# Tead_Aliens_64A_Audio.net
KiCad netlist of a schematic drawn in Altium Designer
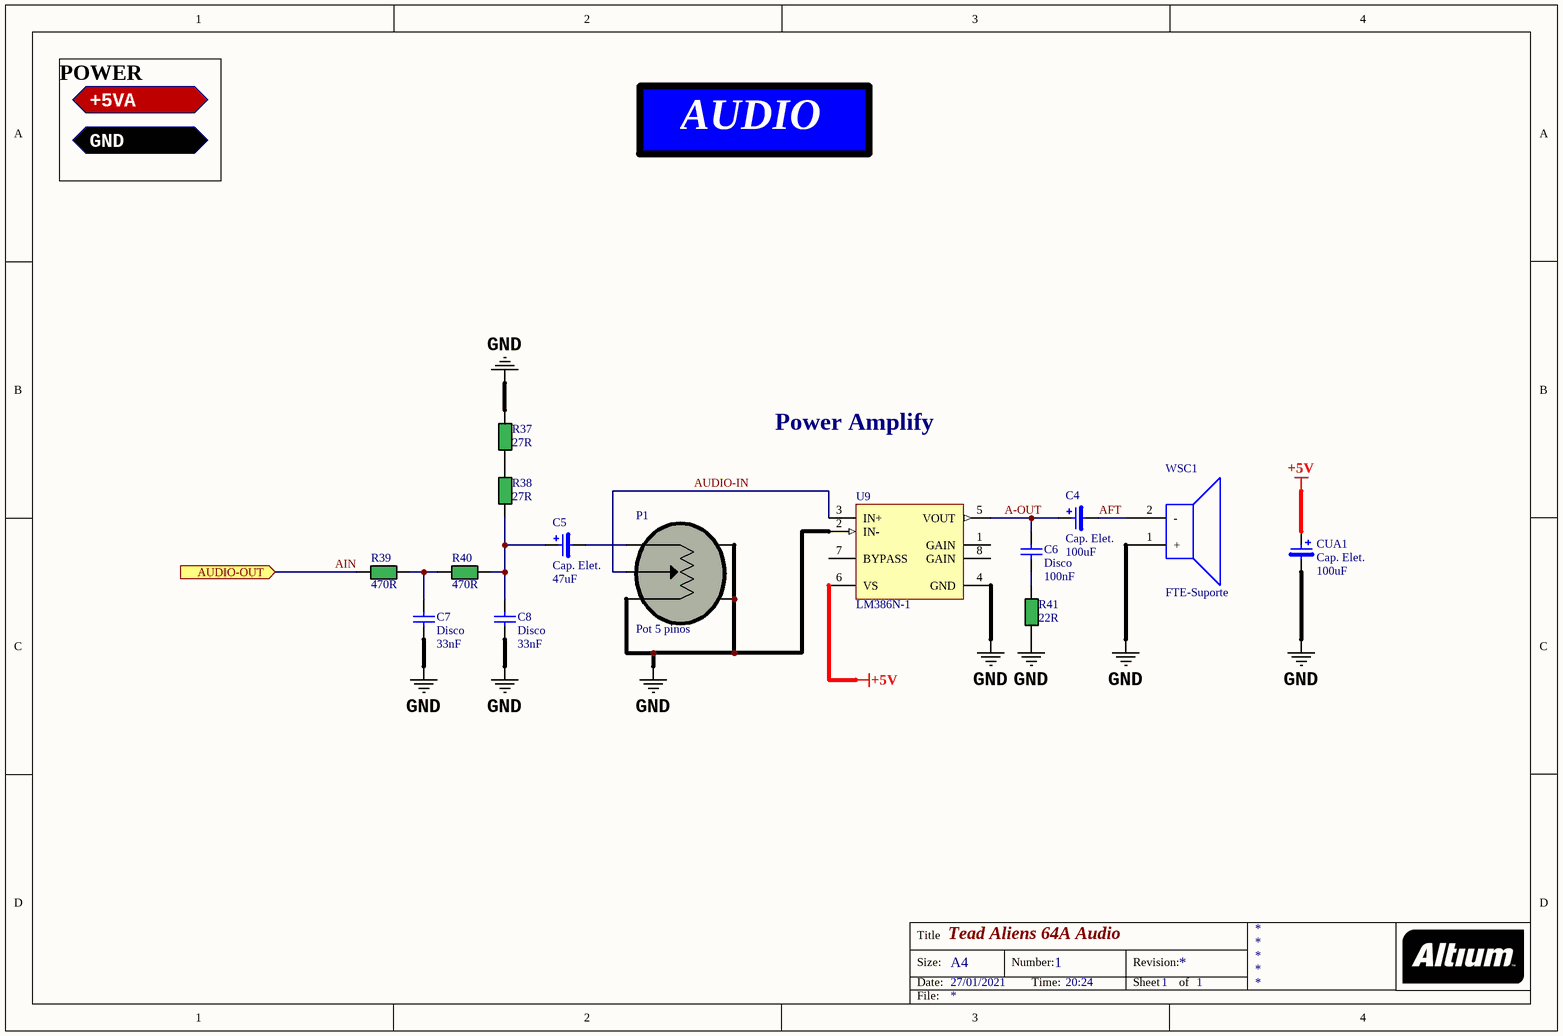
[diagram p0: Tead_Aliens_64A_Audio.SchDoc]

(export (version "E")
  (design (tool "Eeschema 10.0.6"))
  (components
    (comp (ref "C4")
      (value "Cap. Elet.")
      (footprint "CAP_RADIAL_2_10_16")
      (description "Capacitor Radial Eletrolitico")
      (fields (field (name "ALTIUM_VALUE") "100uF"))
      (libsource (lib "NEPERMATH") (part "CAP_RADIAL_ELETROLITICO"))
    )
    (comp (ref "C5")
      (value "Cap. Elet.")
      (footprint "CAP ELE RAD 11mm H")
      (description "Capacitor Radial Eletrolitico")
      (fields (field (name "ALTIUM_VALUE") "47uF"))
      (libsource (lib "NEPERMATH") (part "CAP_RADIAL_ELETROLITICO"))
    )
    (comp (ref "C6")
      (value "Disco")
      (footprint "CAP CER DISK 3MM")
      (description "SMD Capacitor 1210 size")
      (fields (field (name "ALTIUM_VALUE") "100nF"))
      (libsource (lib "NEPERMATH") (part "CAP_DISCO"))
    )
    (comp (ref "C7")
      (value "Disco")
      (footprint "CAP CER DISK 3MM")
      (description "SMD Capacitor 1210 size")
      (fields (field (name "ALTIUM_VALUE") "33nF"))
      (libsource (lib "NEPERMATH") (part "CAP_DISCO"))
    )
    (comp (ref "C8")
      (value "Disco")
      (footprint "CAP CER DISK 3MM")
      (description "SMD Capacitor 1210 size")
      (fields (field (name "ALTIUM_VALUE") "33nF"))
      (libsource (lib "NEPERMATH") (part "CAP_DISCO"))
    )
    (comp (ref "CUA1")
      (value "Cap. Elet.")
      (footprint "CAP_RADIAL_2_10_16")
      (description "Capacitor Radial Eletrolitico")
      (fields (field (name "ALTIUM_VALUE") "100uF"))
      (libsource (lib "NEPERMATH") (part "CAP_RADIAL_ELETROLITICO"))
    )
    (comp (ref "P1")
      (value "Pot 5 pinos")
      (footprint "POT CHINA MICRO")
      (description "Potenciometer 5 pins")
      (libsource (lib "NEPERMATH") (part "POT 5 pinos china"))
    )
    (comp (ref "R37")
      (value "27R")
      (footprint "RES_0805")
      (description "Generic Resistor")
      (fields (field (name "Comment") "Resistor Generic"))
      (libsource (lib "NEPERMATH") (part "Resistor Generic"))
    )
    (comp (ref "R38")
      (value "27R")
      (footprint "RES_0805")
      (description "Generic Resistor")
      (fields (field (name "Comment") "Resistor Generic"))
      (libsource (lib "NEPERMATH") (part "Resistor Generic"))
    )
    (comp (ref "R39")
      (value "470R")
      (footprint "RES_0805")
      (description "Generic Resistor")
      (fields (field (name "Comment") "Resistor Generic"))
      (libsource (lib "") (part "Resistor Generic_1"))
    )
    (comp (ref "R40")
      (value "470R")
      (footprint "RES_0805")
      (description "Generic Resistor")
      (fields (field (name "Comment") "Resistor Generic"))
      (libsource (lib "") (part "Resistor Generic_1"))
    )
    (comp (ref "R41")
      (value "22R")
      (footprint "RES 300 CR25")
      (description "Generic Resistor")
      (fields (field (name "Comment") "Resistor Generic"))
      (libsource (lib "NEPERMATH") (part "Resistor Generic"))
    )
    (comp (ref "U9")
      (value "LM386N-1")
      (footprint "DIP8")
      (description "Low Voltage Audio Power Amplifier")
      (fields
        (field (name "MANUFACTURER") "National Semiconductor")
        (field (name "DIGIKEYPARTNUMBER") "LM386N-1-ND")
      )
      (libsource (lib "NEPERMATH") (part "LM386N-1"))
    )
    (comp (ref "WSC1")
      (value "FTE-Suporte")
      (footprint "FTE-WBC-8OHM-1W-23mm")
      (description "FTE-WBC-8 OHM 23mm X 4.5mm")
      (libsource (lib "NEPERMATH") (part "FTE-WBC 8 OHM 23mm X 4.5mm"))
    )
  )
  (nets
    (net (code "1") (name "+5V") (class "Default")
      (node (ref "CUA1") (pin "1") (pinfunction "1_1") (pintype "passive"))
      (node (ref "U9") (pin "6") (pinfunction "VS_6") (pintype "power_in"))
    )
    (net (code "3") (name "/A-OUT") (class "Default")
      (node (ref "C4") (pin "1") (pinfunction "1_1") (pintype "passive"))
      (node (ref "C6") (pin "2") (pinfunction "2_2") (pintype "passive"))
      (node (ref "U9") (pin "5") (pinfunction "VOUT_5") (pintype "output"))
    )
    (net (code "4") (name "/AFT") (class "Default")
      (node (ref "C4") (pin "2") (pinfunction "2_2") (pintype "passive"))
      (node (ref "WSC1") (pin "2") (pinfunction "-_2") (pintype "passive"))
    )
    (net (code "5") (name "/AIN") (class "Default")
      (node (ref "R39") (pin "1") (pinfunction "1_1") (pintype "passive"))
    )
    (net (code "6") (name "/AUDIO-IN") (class "Default")
      (node (ref "P1") (pin "2") (pinfunction "2_2") (pintype "passive"))
      (node (ref "U9") (pin "3") (pinfunction "IN+_3") (pintype "passive"))
    )
    (net (code "7") (name "GND") (class "Default")
      (node (ref "C7") (pin "1") (pinfunction "1_1") (pintype "passive"))
      (node (ref "C8") (pin "1") (pinfunction "1_1") (pintype "passive"))
      (node (ref "CUA1") (pin "2") (pinfunction "2_2") (pintype "passive"))
      (node (ref "P1") (pin "3") (pinfunction "3_3") (pintype "passive"))
      (node (ref "P1") (pin "4") (pinfunction "4_4") (pintype "passive"))
      (node (ref "P1") (pin "5") (pinfunction "5_5") (pintype "passive"))
      (node (ref "R37") (pin "2") (pinfunction "2_2") (pintype "passive"))
      (node (ref "R41") (pin "1") (pinfunction "1_1") (pintype "passive"))
      (node (ref "U9") (pin "2") (pinfunction "IN-_2") (pintype "input"))
      (node (ref "U9") (pin "4") (pinfunction "GND_4") (pintype "power_in"))
      (node (ref "WSC1") (pin "1") (pinfunction "+_1") (pintype "passive"))
    )
    (net (code "8") (name "Net-(C5-Pad1)") (class "Default")
      (node (ref "C5") (pin "1") (pinfunction "1_1") (pintype "passive"))
      (node (ref "C8") (pin "2") (pinfunction "2_2") (pintype "passive"))
      (node (ref "R38") (pin "1") (pinfunction "1_1") (pintype "passive"))
      (node (ref "R40") (pin "2") (pinfunction "2_2") (pintype "passive"))
    )
    (net (code "9") (name "Net-(C5-Pad2)") (class "Default")
      (node (ref "C5") (pin "2") (pinfunction "2_2") (pintype "passive"))
      (node (ref "P1") (pin "1") (pinfunction "1_1") (pintype "passive"))
    )
    (net (code "10") (name "Net-(C6-Pad1)") (class "Default")
      (node (ref "C6") (pin "1") (pinfunction "1_1") (pintype "passive"))
      (node (ref "R41") (pin "2") (pinfunction "2_2") (pintype "passive"))
    )
    (net (code "11") (name "Net-(C7-Pad2)") (class "Default")
      (node (ref "C7") (pin "2") (pinfunction "2_2") (pintype "passive"))
      (node (ref "R39") (pin "2") (pinfunction "2_2") (pintype "passive"))
      (node (ref "R40") (pin "1") (pinfunction "1_1") (pintype "passive"))
    )
    (net (code "12") (name "Net-(R37-Pad1)") (class "Default")
      (node (ref "R37") (pin "1") (pinfunction "1_1") (pintype "passive"))
      (node (ref "R38") (pin "2") (pinfunction "2_2") (pintype "passive"))
    )
    (net (code "13") (name "unconnected-(U9-BYPASS-Pad7)") (class "Default")
      (node (ref "U9") (pin "7") (pinfunction "BYPASS_7") (pintype "passive"))
    )
    (net (code "14") (name "unconnected-(U9-GAIN-Pad1)") (class "Default")
      (node (ref "U9") (pin "1") (pinfunction "GAIN_1") (pintype "passive"))
    )
    (net (code "15") (name "unconnected-(U9-GAIN-Pad8)") (class "Default")
      (node (ref "U9") (pin "8") (pinfunction "GAIN_8") (pintype "passive"))
    )
  )
)
